# E1706RS485.net
KiCad netlist of a schematic drawn in Altium Designer
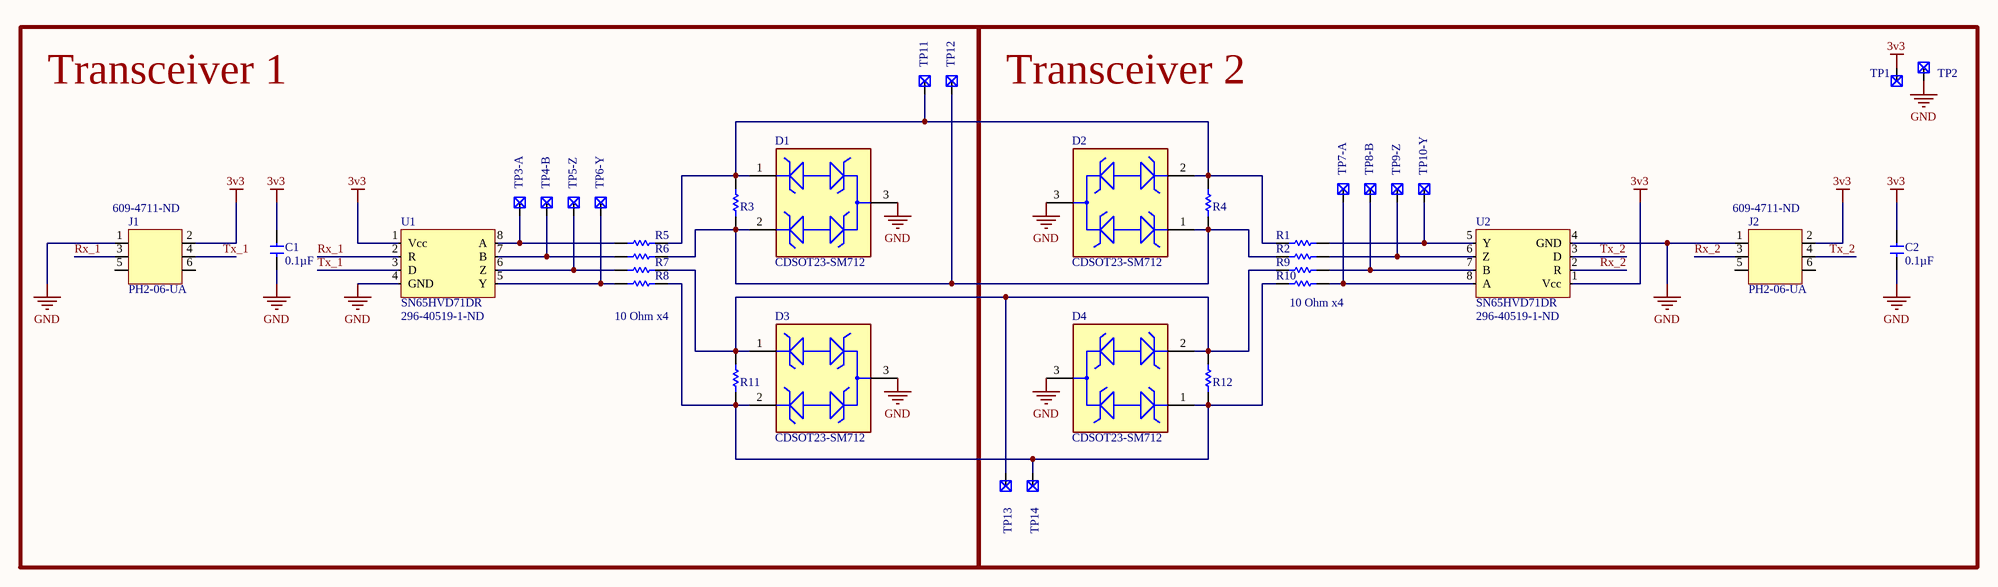
[diagram p0: E1706RS485.SchDoc]

(export (version "E")
  (design (tool "Eeschema 10.0.6"))
  (components
    (comp (ref "C1")
      (value "0.1uF")
      (footprint "CAPC1608N")
      (description "CAP CER 0.1UF 25V 10% X7R 0603")
      (fields
        (field (name "MANUFACTURER") "Murata Electronics North America")
        (field (name "TOLERANCE") "±10%")
        (field (name "CAPACITANCE") "0.1µF")
      )
      (libsource (lib "Erico_Ignitor") (part "Cap_0.1uF_25V_0603"))
    )
    (comp (ref "C2")
      (value "0.1uF")
      (footprint "CAPC1608N")
      (description "CAP CER 0.1UF 25V 10% X7R 0603")
      (fields
        (field (name "MANUFACTURER") "Murata Electronics North America")
        (field (name "TOLERANCE") "±10%")
        (field (name "CAPACITANCE") "0.1µF")
      )
      (libsource (lib "Erico_Ignitor") (part "Cap_0.1uF_25V_0603"))
    )
    (comp (ref "D1")
      (value "CDSOT23-SM712")
      (footprint "FP-SOT23-MFG")
      (description "TVS DIODE 7V/12V 14V/26V SOT23-3")
      (fields
        (field (name "MANUFACTURER") "Bourns Inc.")
        (field (name "OCTOPART") "https://octopart.com/cdsot23-sm712-bourns-7576327")
      )
      (libsource (lib "Altium Content Vault") (part "81303f94231262926866863442dad16"))
    )
    (comp (ref "D2")
      (value "CDSOT23-SM712")
      (footprint "FP-SOT23-MFG")
      (description "TVS DIODE 7V/12V 14V/26V SOT23-3")
      (fields
        (field (name "MANUFACTURER") "Bourns Inc.")
        (field (name "OCTOPART") "https://octopart.com/cdsot23-sm712-bourns-7576327")
      )
      (libsource (lib "Altium Content Vault") (part "81303f94231262926866863442dad16"))
    )
    (comp (ref "D3")
      (value "CDSOT23-SM712")
      (footprint "FP-SOT23-MFG")
      (description "TVS DIODE 7V/12V 14V/26V SOT23-3")
      (fields
        (field (name "MANUFACTURER") "Bourns Inc.")
        (field (name "OCTOPART") "https://octopart.com/cdsot23-sm712-bourns-7576327")
      )
      (libsource (lib "Altium Content Vault") (part "81303f94231262926866863442dad16"))
    )
    (comp (ref "D4")
      (value "CDSOT23-SM712")
      (footprint "FP-SOT23-MFG")
      (description "TVS DIODE 7V/12V 14V/26V SOT23-3")
      (fields
        (field (name "MANUFACTURER") "Bourns Inc.")
        (field (name "OCTOPART") "https://octopart.com/cdsot23-sm712-bourns-7576327")
      )
      (libsource (lib "Altium Content Vault") (part "81303f94231262926866863442dad16"))
    )
    (comp (ref "J1")
      (value "PH2-06-UA")
      (footprint "PH2-06-UA")
      (description "Conn;  Rect;  Header;  6 Pos;  2.54mm Pitch;  Bergstik II;  Self Ret;  High Temp")
      (fields
        (field (name "SUPPLIER PART NUMBER 1") "609-4711-ND")
        (field (name "MANUFACTURER") "Amphenol ICC / FCI")
        (field (name "MANUFACTURER PART NUMBER") "69192-406HLF")
      )
      (libsource (lib "SchLibrary") (part "PH2-06-UA"))
    )
    (comp (ref "J2")
      (value "PH2-06-UA")
      (footprint "PH2-06-UA")
      (description "Conn;  Rect;  Header;  6 Pos;  2.54mm Pitch;  Bergstik II;  Self Ret;  High Temp")
      (fields
        (field (name "SUPPLIER PART NUMBER 1") "609-4711-ND")
        (field (name "MANUFACTURER") "Amphenol ICC / FCI")
        (field (name "MANUFACTURER PART NUMBER") "69192-406HLF")
      )
      (libsource (lib "SchLibrary") (part "PH2-06-UA"))
    )
    (comp (ref "R1")
      (value "Res_10_0805")
      (footprint "RESC2012N")
      (description "RES 10 OHM 1/8W 1% 0805")
      (fields (field (name "MANUFACTURER") "Vishay Dale") (field (name "TOLERANCE") "±1%"))
      (libsource (lib "Erico_Ignitor") (part "Res_10_0805"))
    )
    (comp (ref "R2")
      (value "Res_10_0805")
      (footprint "RESC2012N")
      (description "RES 10 OHM 1/8W 1% 0805")
      (fields (field (name "MANUFACTURER") "Vishay Dale") (field (name "TOLERANCE") "±1%"))
      (libsource (lib "Erico_Ignitor") (part "Res_10_0805"))
    )
    (comp (ref "R3")
      (value "Res_120_0805")
      (footprint "RESC2012N")
      (description "RES 120 OHM 1/8W 1% 0805")
      (libsource (lib "Erico_Ignitor") (part "Res_120_0805"))
    )
    (comp (ref "R4")
      (value "Res_120_0805")
      (footprint "RESC2012N")
      (description "RES 120 OHM 1/8W 1% 0805")
      (libsource (lib "Erico_Ignitor") (part "Res_120_0805"))
    )
    (comp (ref "R5")
      (value "Res_10_0805")
      (footprint "RESC2012N")
      (description "RES 10 OHM 1/8W 1% 0805")
      (fields (field (name "MANUFACTURER") "Vishay Dale") (field (name "TOLERANCE") "±1%"))
      (libsource (lib "Erico_Ignitor") (part "Res_10_0805"))
    )
    (comp (ref "R6")
      (value "Res_10_0805")
      (footprint "RESC2012N")
      (description "RES 10 OHM 1/8W 1% 0805")
      (fields (field (name "MANUFACTURER") "Vishay Dale") (field (name "TOLERANCE") "±1%"))
      (libsource (lib "Erico_Ignitor") (part "Res_10_0805"))
    )
    (comp (ref "R7")
      (value "Res_10_0805")
      (footprint "RESC2012N")
      (description "RES 10 OHM 1/8W 1% 0805")
      (fields (field (name "MANUFACTURER") "Vishay Dale") (field (name "TOLERANCE") "±1%"))
      (libsource (lib "Erico_Ignitor") (part "Res_10_0805"))
    )
    (comp (ref "R8")
      (value "Res_10_0805")
      (footprint "RESC2012N")
      (description "RES 10 OHM 1/8W 1% 0805")
      (fields (field (name "MANUFACTURER") "Vishay Dale") (field (name "TOLERANCE") "±1%"))
      (libsource (lib "Erico_Ignitor") (part "Res_10_0805"))
    )
    (comp (ref "R9")
      (value "Res_10_0805")
      (footprint "RESC2012N")
      (description "RES 10 OHM 1/8W 1% 0805")
      (fields (field (name "MANUFACTURER") "Vishay Dale") (field (name "TOLERANCE") "±1%"))
      (libsource (lib "Erico_Ignitor") (part "Res_10_0805"))
    )
    (comp (ref "R10")
      (value "Res_10_0805")
      (footprint "RESC2012N")
      (description "RES 10 OHM 1/8W 1% 0805")
      (fields (field (name "MANUFACTURER") "Vishay Dale") (field (name "TOLERANCE") "±1%"))
      (libsource (lib "Erico_Ignitor") (part "Res_10_0805"))
    )
    (comp (ref "R11")
      (value "Res_120_0805")
      (footprint "RESC2012N")
      (description "RES 120 OHM 1/8W 1% 0805")
      (libsource (lib "Erico_Ignitor") (part "Res_120_0805"))
    )
    (comp (ref "R12")
      (value "Res_120_0805")
      (footprint "RESC2012N")
      (description "RES 120 OHM 1/8W 1% 0805")
      (libsource (lib "Erico_Ignitor") (part "Res_120_0805"))
    )
    (comp (ref "TP1")
      (value "Testpoint")
      (footprint "TEST_POINT_TH")
      (libsource (lib "") (part "Test Point_1_1"))
    )
    (comp (ref "TP2")
      (value "Testpoint")
      (footprint "TEST_POINT_TH")
      (libsource (lib "Erico_Ignitor") (part "Test Point_1"))
    )
    (comp (ref "TP3-A")
      (value "Testpoint")
      (footprint "TEST_POINT_TH")
      (libsource (lib "Erico_Ignitor") (part "Test Point_1"))
    )
    (comp (ref "TP4-B")
      (value "Testpoint")
      (footprint "TEST_POINT_TH")
      (libsource (lib "Erico_Ignitor") (part "Test Point_1"))
    )
    (comp (ref "TP5-Z")
      (value "Testpoint")
      (footprint "TEST_POINT_TH")
      (libsource (lib "Erico_Ignitor") (part "Test Point_1"))
    )
    (comp (ref "TP6-Y")
      (value "Testpoint")
      (footprint "TEST_POINT_TH")
      (libsource (lib "Erico_Ignitor") (part "Test Point_1"))
    )
    (comp (ref "TP7-A")
      (value "Testpoint")
      (footprint "TEST_POINT_TH")
      (libsource (lib "Erico_Ignitor") (part "Test Point_1"))
    )
    (comp (ref "TP8-B")
      (value "Testpoint")
      (footprint "TEST_POINT_TH")
      (libsource (lib "Erico_Ignitor") (part "Test Point_1"))
    )
    (comp (ref "TP9-Z")
      (value "Testpoint")
      (footprint "TEST_POINT_TH")
      (libsource (lib "Erico_Ignitor") (part "Test Point_1"))
    )
    (comp (ref "TP10-Y")
      (value "Testpoint")
      (footprint "TEST_POINT_TH")
      (libsource (lib "Erico_Ignitor") (part "Test Point_1"))
    )
    (comp (ref "TP11")
      (value "Testpoint")
      (footprint "TEST_POINT_TH")
      (libsource (lib "Erico_Ignitor") (part "Test Point_1"))
    )
    (comp (ref "TP12")
      (value "Testpoint")
      (footprint "TEST_POINT_TH")
      (libsource (lib "Erico_Ignitor") (part "Test Point_1"))
    )
    (comp (ref "TP13")
      (value "Testpoint")
      (footprint "TEST_POINT_TH")
      (libsource (lib "") (part "Test Point_1_1"))
    )
    (comp (ref "TP14")
      (value "Testpoint")
      (footprint "TEST_POINT_TH")
      (libsource (lib "") (part "Test Point_1_1"))
    )
    (comp (ref "U1")
      (value "SN65HVD71DR")
      (footprint "SN65HVD71DR")
      (description "Single Transmitter/Receiver RS-485 8-Pin SOIC T/R")
      (fields
        (field (name "SUPPLIER PART NUMBER 1") "296-40519-1-ND")
        (field (name "MANUFACTURER") "Texas Instruments")
      )
      (libsource (lib "SchLibrary") (part "SN65HVD71DR"))
    )
    (comp (ref "U2")
      (value "SN65HVD71DR")
      (footprint "SN65HVD71DR")
      (description "Single Transmitter/Receiver RS-485 8-Pin SOIC T/R")
      (fields
        (field (name "SUPPLIER PART NUMBER 1") "296-40519-1-ND")
        (field (name "MANUFACTURER") "Texas Instruments")
      )
      (libsource (lib "") (part "SN65HVD71DR_1"))
    )
  )
  (nets
    (net (code "1") (name "/Rx_1") (class "Default")
      (node (ref "J1") (pin "3") (pinfunction "3_3") (pintype "passive"))
      (node (ref "U1") (pin "2") (pinfunction "R_2") (pintype "passive"))
    )
    (net (code "2") (name "/Rx_2") (class "Default")
      (node (ref "J2") (pin "3") (pinfunction "3_3") (pintype "passive"))
      (node (ref "U2") (pin "2") (pinfunction "R_2") (pintype "passive"))
    )
    (net (code "3") (name "/Tx_1") (class "Default")
      (node (ref "J1") (pin "4") (pinfunction "4_4") (pintype "passive"))
      (node (ref "U1") (pin "3") (pinfunction "D_3") (pintype "passive"))
    )
    (net (code "4") (name "/Tx_2") (class "Default")
      (node (ref "J2") (pin "4") (pinfunction "4_4") (pintype "passive"))
      (node (ref "U2") (pin "3") (pinfunction "D_3") (pintype "passive"))
    )
    (net (code "5") (name "3v3") (class "Default")
      (node (ref "C1") (pin "2") (pinfunction "2_2") (pintype "passive"))
      (node (ref "C2") (pin "2") (pinfunction "2_2") (pintype "passive"))
      (node (ref "J1") (pin "2") (pinfunction "2_2") (pintype "passive"))
      (node (ref "J2") (pin "2") (pinfunction "2_2") (pintype "passive"))
      (node (ref "TP1") (pin "1") (pinfunction "Test_1") (pintype "passive"))
      (node (ref "U1") (pin "1") (pinfunction "Vcc_1") (pintype "passive"))
      (node (ref "U2") (pin "1") (pinfunction "Vcc_1") (pintype "passive"))
    )
    (net (code "6") (name "GND") (class "Default")
      (node (ref "C1") (pin "1") (pinfunction "1_1") (pintype "passive"))
      (node (ref "C2") (pin "1") (pinfunction "1_1") (pintype "passive"))
      (node (ref "D1") (pin "3") (pinfunction "3_3") (pintype "passive"))
      (node (ref "D2") (pin "3") (pinfunction "3_3") (pintype "passive"))
      (node (ref "D3") (pin "3") (pinfunction "3_3") (pintype "passive"))
      (node (ref "D4") (pin "3") (pinfunction "3_3") (pintype "passive"))
      (node (ref "J1") (pin "1") (pinfunction "1_1") (pintype "passive"))
      (node (ref "J2") (pin "1") (pinfunction "1_1") (pintype "passive"))
      (node (ref "TP2") (pin "1") (pinfunction "Test_1") (pintype "passive"))
      (node (ref "U1") (pin "4") (pinfunction "GND_4") (pintype "passive"))
      (node (ref "U2") (pin "4") (pinfunction "GND_4") (pintype "passive"))
    )
    (net (code "7") (name "Net-(TP3-A-Test)") (class "Default")
      (node (ref "R5") (pin "1") (pinfunction "1_1") (pintype "passive"))
      (node (ref "TP3-A") (pin "1") (pinfunction "Test_1") (pintype "passive"))
      (node (ref "U1") (pin "8") (pinfunction "A_8") (pintype "passive"))
    )
    (net (code "8") (name "Net-(TP4-B-Test)") (class "Default")
      (node (ref "R6") (pin "1") (pinfunction "1_1") (pintype "passive"))
      (node (ref "TP4-B") (pin "1") (pinfunction "Test_1") (pintype "passive"))
      (node (ref "U1") (pin "7") (pinfunction "B_7") (pintype "passive"))
    )
    (net (code "9") (name "Net-(TP5-Z-Test)") (class "Default")
      (node (ref "R7") (pin "1") (pinfunction "1_1") (pintype "passive"))
      (node (ref "TP5-Z") (pin "1") (pinfunction "Test_1") (pintype "passive"))
      (node (ref "U1") (pin "6") (pinfunction "Z_6") (pintype "passive"))
    )
    (net (code "10") (name "Net-(TP6-Y-Test)") (class "Default")
      (node (ref "R8") (pin "1") (pinfunction "1_1") (pintype "passive"))
      (node (ref "TP6-Y") (pin "1") (pinfunction "Test_1") (pintype "passive"))
      (node (ref "U1") (pin "5") (pinfunction "Y_5") (pintype "passive"))
    )
    (net (code "11") (name "Net-(TP7-A-Test)") (class "Default")
      (node (ref "R10") (pin "2") (pinfunction "2_2") (pintype "passive"))
      (node (ref "TP7-A") (pin "1") (pinfunction "Test_1") (pintype "passive"))
      (node (ref "U2") (pin "8") (pinfunction "A_8") (pintype "passive"))
    )
    (net (code "12") (name "Net-(TP8-B-Test)") (class "Default")
      (node (ref "R9") (pin "2") (pinfunction "2_2") (pintype "passive"))
      (node (ref "TP8-B") (pin "1") (pinfunction "Test_1") (pintype "passive"))
      (node (ref "U2") (pin "7") (pinfunction "B_7") (pintype "passive"))
    )
    (net (code "13") (name "Net-(TP9-Z-Test)") (class "Default")
      (node (ref "R2") (pin "2") (pinfunction "2_2") (pintype "passive"))
      (node (ref "TP9-Z") (pin "1") (pinfunction "Test_1") (pintype "passive"))
      (node (ref "U2") (pin "6") (pinfunction "Z_6") (pintype "passive"))
    )
    (net (code "14") (name "Net-(TP10-Y-Test)") (class "Default")
      (node (ref "R1") (pin "2") (pinfunction "2_2") (pintype "passive"))
      (node (ref "TP10-Y") (pin "1") (pinfunction "Test_1") (pintype "passive"))
      (node (ref "U2") (pin "5") (pinfunction "Y_5") (pintype "passive"))
    )
    (net (code "15") (name "Net-(TP11-Test)") (class "Default")
      (node (ref "D1") (pin "1") (pinfunction "1_1") (pintype "passive"))
      (node (ref "D2") (pin "2") (pinfunction "2_2") (pintype "passive"))
      (node (ref "R1") (pin "1") (pinfunction "1_1") (pintype "passive"))
      (node (ref "R3") (pin "2") (pinfunction "2_2") (pintype "passive"))
      (node (ref "R4") (pin "2") (pinfunction "2_2") (pintype "passive"))
      (node (ref "R5") (pin "2") (pinfunction "2_2") (pintype "passive"))
      (node (ref "TP11") (pin "1") (pinfunction "Test_1") (pintype "passive"))
    )
    (net (code "16") (name "Net-(TP12-Test)") (class "Default")
      (node (ref "D1") (pin "2") (pinfunction "2_2") (pintype "passive"))
      (node (ref "D2") (pin "1") (pinfunction "1_1") (pintype "passive"))
      (node (ref "R2") (pin "1") (pinfunction "1_1") (pintype "passive"))
      (node (ref "R3") (pin "1") (pinfunction "1_1") (pintype "passive"))
      (node (ref "R4") (pin "1") (pinfunction "1_1") (pintype "passive"))
      (node (ref "R6") (pin "2") (pinfunction "2_2") (pintype "passive"))
      (node (ref "TP12") (pin "1") (pinfunction "Test_1") (pintype "passive"))
    )
    (net (code "17") (name "Net-(TP13-Test)") (class "Default")
      (node (ref "D3") (pin "1") (pinfunction "1_1") (pintype "passive"))
      (node (ref "D4") (pin "2") (pinfunction "2_2") (pintype "passive"))
      (node (ref "R11") (pin "2") (pinfunction "2_2") (pintype "passive"))
      (node (ref "R12") (pin "2") (pinfunction "2_2") (pintype "passive"))
      (node (ref "R7") (pin "2") (pinfunction "2_2") (pintype "passive"))
      (node (ref "R9") (pin "1") (pinfunction "1_1") (pintype "passive"))
      (node (ref "TP13") (pin "1") (pinfunction "Test_1") (pintype "passive"))
    )
    (net (code "18") (name "Net-(TP14-Test)") (class "Default")
      (node (ref "D3") (pin "2") (pinfunction "2_2") (pintype "passive"))
      (node (ref "D4") (pin "1") (pinfunction "1_1") (pintype "passive"))
      (node (ref "R10") (pin "1") (pinfunction "1_1") (pintype "passive"))
      (node (ref "R11") (pin "1") (pinfunction "1_1") (pintype "passive"))
      (node (ref "R12") (pin "1") (pinfunction "1_1") (pintype "passive"))
      (node (ref "R8") (pin "2") (pinfunction "2_2") (pintype "passive"))
      (node (ref "TP14") (pin "1") (pinfunction "Test_1") (pintype "passive"))
    )
    (net (code "19") (name "unconnected-(J1-Pad5)") (class "Default")
      (node (ref "J1") (pin "5") (pinfunction "5_5") (pintype "passive"))
    )
    (net (code "20") (name "unconnected-(J1-Pad6)") (class "Default")
      (node (ref "J1") (pin "6") (pinfunction "6_6") (pintype "passive"))
    )
    (net (code "21") (name "unconnected-(J2-Pad5)") (class "Default")
      (node (ref "J2") (pin "5") (pinfunction "5_5") (pintype "passive"))
    )
    (net (code "22") (name "unconnected-(J2-Pad6)") (class "Default")
      (node (ref "J2") (pin "6") (pinfunction "6_6") (pintype "passive"))
    )
  )
)
